# cryobondr-qbit2-pqc-rev2.net
KiCad netlist of a schematic drawn in EAGLE
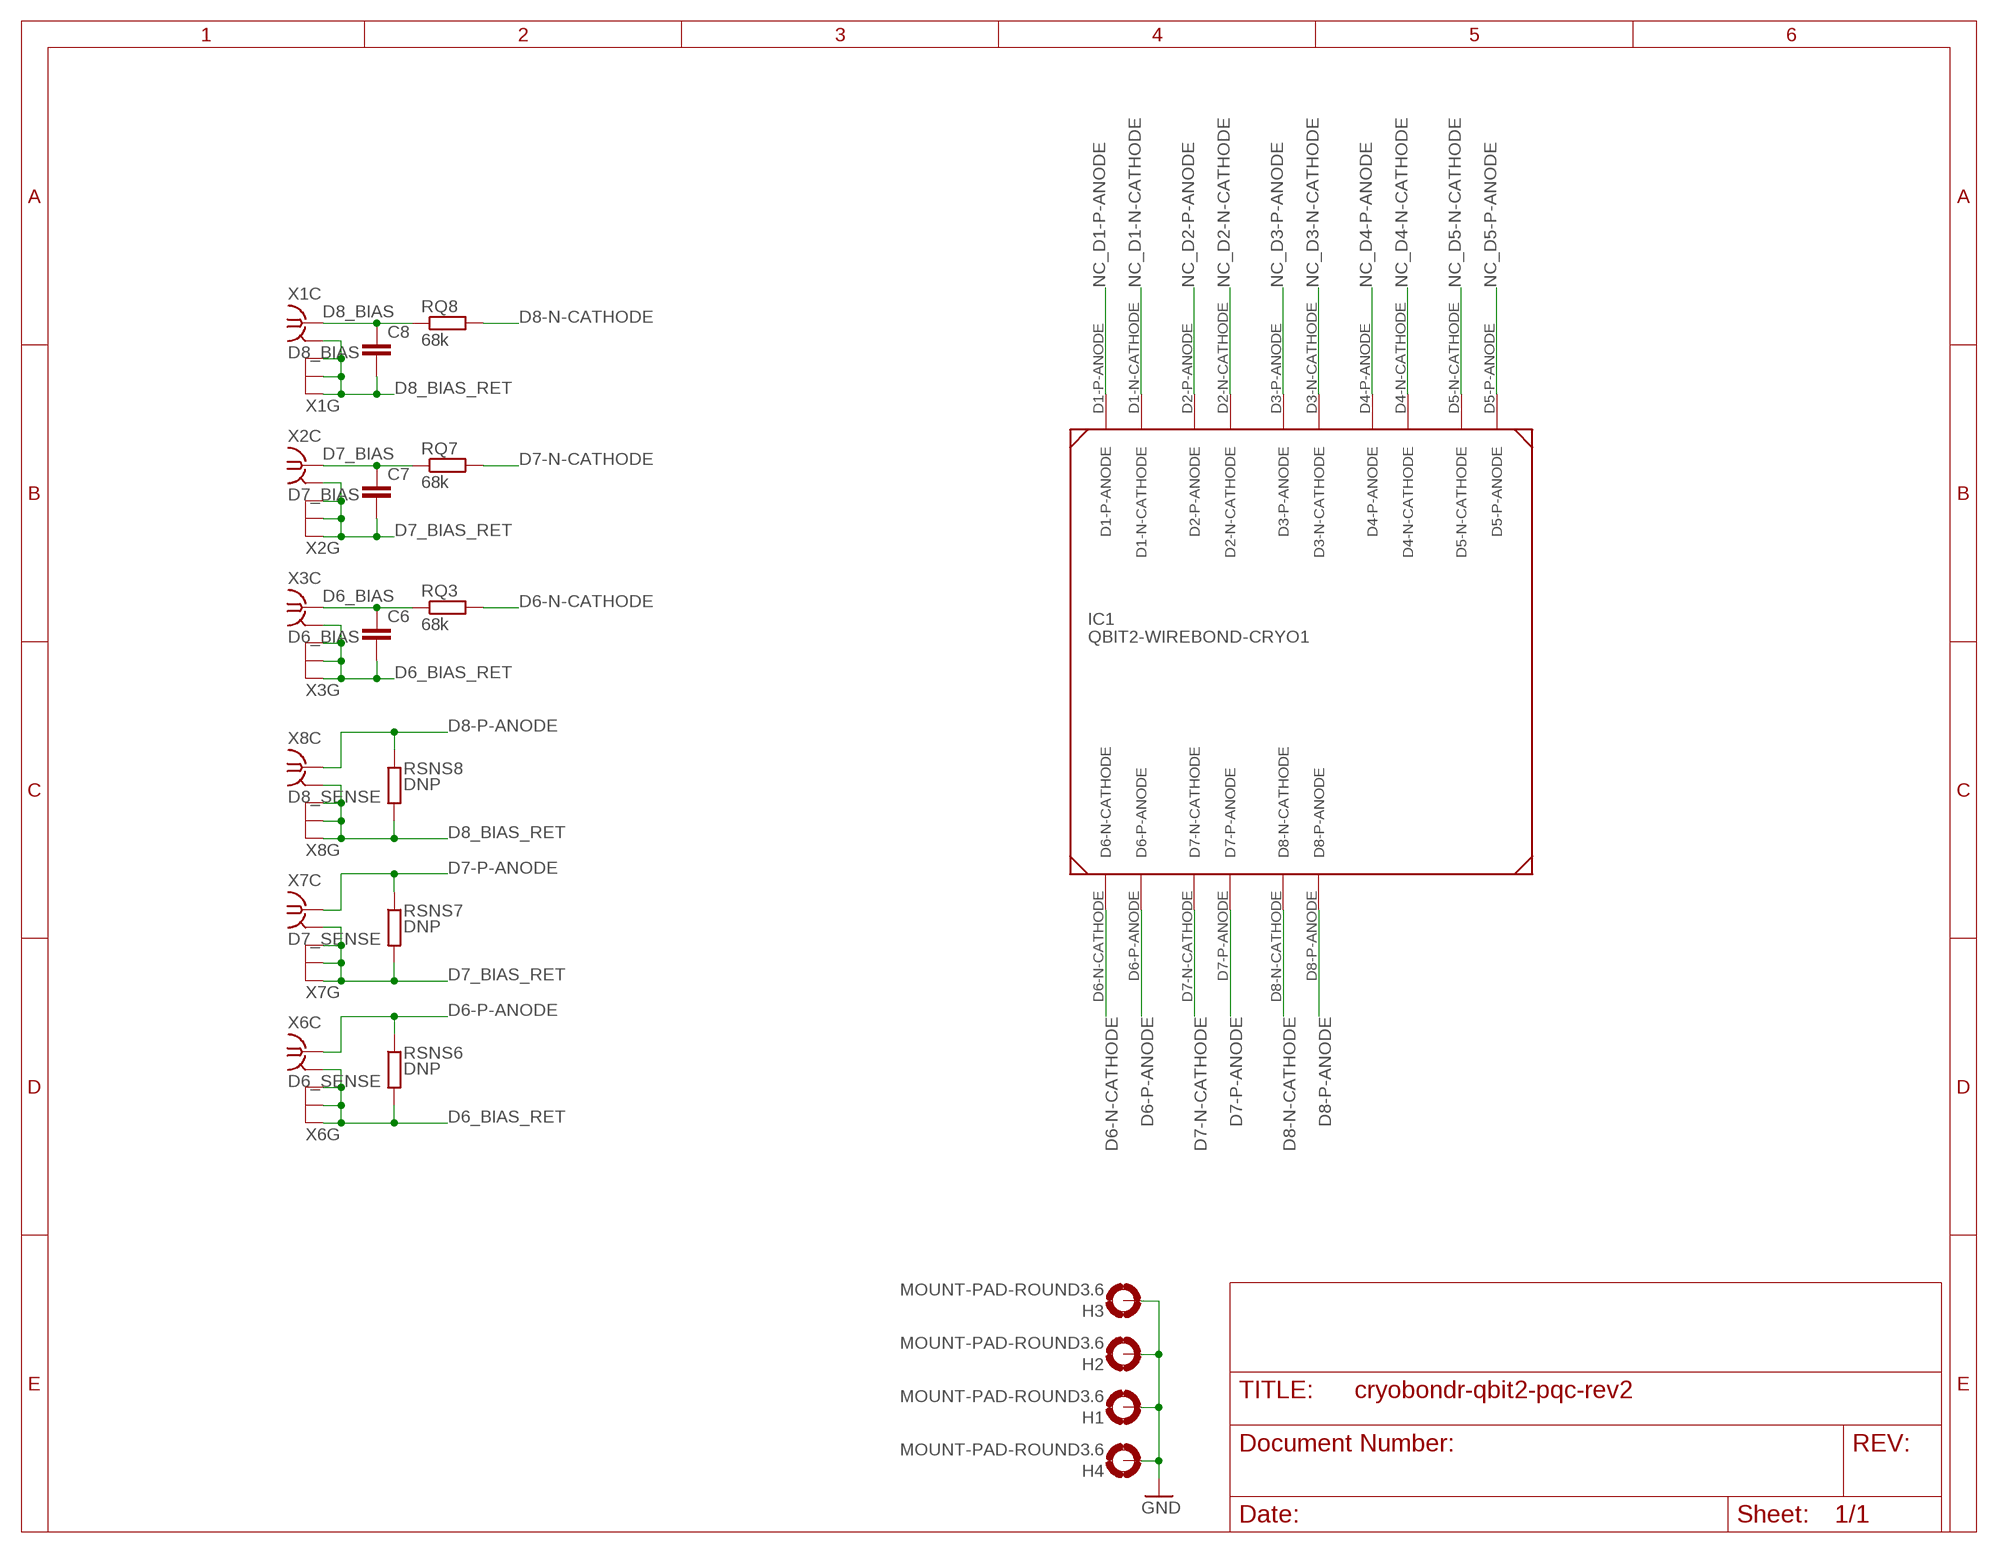
[diagram p0: schematic, sheet 1]

(export (version "E")
  (design (tool "Eeschema 10.0.6"))
  (components
    (comp (ref "C6")
      (value "C-EUC0603")
      (footprint "eagle-import:C0603")
      (libsource (lib "eagle-import") (part "C-EUC0603"))
    )
    (comp (ref "C7")
      (value "C-EUC0603")
      (footprint "eagle-import:C0603")
      (libsource (lib "eagle-import") (part "C-EUC0603"))
    )
    (comp (ref "C8")
      (value "C-EUC0603")
      (footprint "eagle-import:C0603")
      (libsource (lib "eagle-import") (part "C-EUC0603"))
    )
    (comp (ref "H1")
      (value "MOUNT-PAD-ROUND3.6")
      (footprint "eagle-import:3,6-PAD")
      (libsource (lib "eagle-import") (part "MOUNT-PAD-ROUND3.6"))
    )
    (comp (ref "H2")
      (value "MOUNT-PAD-ROUND3.6")
      (footprint "eagle-import:3,6-PAD")
      (libsource (lib "eagle-import") (part "MOUNT-PAD-ROUND3.6"))
    )
    (comp (ref "H3")
      (value "MOUNT-PAD-ROUND3.6")
      (footprint "eagle-import:3,6-PAD")
      (libsource (lib "eagle-import") (part "MOUNT-PAD-ROUND3.6"))
    )
    (comp (ref "H4")
      (value "MOUNT-PAD-ROUND3.6")
      (footprint "eagle-import:3,6-PAD")
      (libsource (lib "eagle-import") (part "MOUNT-PAD-ROUND3.6"))
    )
    (comp (ref "IC1")
      (value "QBIT2-WIREBOND-CRYO1")
      (footprint "eagle-import:QBIT2-WIREBOND-CRYO1")
      (libsource (lib "eagle-import") (part "QBIT2-WIREBOND-CRYO1"))
    )
    (comp (ref "RQ3")
      (value "68k")
      (footprint "eagle-import:R0603")
      (libsource (lib "eagle-import") (part "R-EU_R0603"))
    )
    (comp (ref "RQ7")
      (value "68k")
      (footprint "eagle-import:R0603")
      (libsource (lib "eagle-import") (part "R-EU_R0603"))
    )
    (comp (ref "RQ8")
      (value "68k")
      (footprint "eagle-import:R0603")
      (libsource (lib "eagle-import") (part "R-EU_R0603"))
    )
    (comp (ref "RSNS6")
      (value "DNP")
      (footprint "eagle-import:R0603")
      (libsource (lib "eagle-import") (part "R-EU_R0603"))
    )
    (comp (ref "RSNS7")
      (value "DNP")
      (footprint "eagle-import:R0603")
      (libsource (lib "eagle-import") (part "R-EU_R0603"))
    )
    (comp (ref "RSNS8")
      (value "DNP")
      (footprint "eagle-import:R0603")
      (libsource (lib "eagle-import") (part "R-EU_R0603"))
    )
    (comp (ref "X1")
      (value "D8_BIAS")
      (footprint "eagle-import:MMCX-SMT-BIGPADS")
      (libsource (lib "eagle-import") (part "MMCXBIGPAD"))
    )
    (comp (ref "X2")
      (value "D7_BIAS")
      (footprint "eagle-import:MMCX-SMT-BIGPADS")
      (libsource (lib "eagle-import") (part "MMCXBIGPAD"))
    )
    (comp (ref "X3")
      (value "D6_BIAS")
      (footprint "eagle-import:MMCX-SMT-BIGPADS")
      (libsource (lib "eagle-import") (part "MMCXBIGPAD"))
    )
    (comp (ref "X6")
      (value "D6_SENSE")
      (footprint "eagle-import:MMCX-SMT-BIGPADS")
      (libsource (lib "eagle-import") (part "MMCXBIGPAD"))
    )
    (comp (ref "X7")
      (value "D7_SENSE")
      (footprint "eagle-import:MMCX-SMT-BIGPADS")
      (libsource (lib "eagle-import") (part "MMCXBIGPAD"))
    )
    (comp (ref "X8")
      (value "D8_SENSE")
      (footprint "eagle-import:MMCX-SMT-BIGPADS")
      (libsource (lib "eagle-import") (part "MMCXBIGPAD"))
    )
  )
  (nets
    (net (code "1") (name "/D6-N-CATHODE") (class "Default")
      (node (ref "IC1") (pin "D6-N-CATHODE") (pinfunction "D6-N-CATHODE_D6-N-CATHODE") (pintype "bidirectional"))
      (node (ref "RQ3") (pin "2") (pinfunction "2_2") (pintype "passive"))
    )
    (net (code "2") (name "/D6-P-ANODE") (class "Default")
      (node (ref "IC1") (pin "D6-P-ANODE") (pinfunction "D6-P-ANODE_D6-P-ANODE") (pintype "bidirectional"))
      (node (ref "RSNS6") (pin "1") (pinfunction "1_1") (pintype "passive"))
      (node (ref "X6") (pin "S") (pinfunction "1_S") (pintype "passive"))
    )
    (net (code "3") (name "/D6_BIAS") (class "Default")
      (node (ref "C6") (pin "1") (pinfunction "1_1") (pintype "passive"))
      (node (ref "RQ3") (pin "1") (pinfunction "1_1") (pintype "passive"))
      (node (ref "X3") (pin "S") (pinfunction "1_S") (pintype "passive"))
    )
    (net (code "4") (name "/D6_BIAS_RET") (class "Default")
      (node (ref "C6") (pin "2") (pinfunction "2_2") (pintype "passive"))
      (node (ref "RSNS6") (pin "2") (pinfunction "2_2") (pintype "passive"))
      (node (ref "X3") (pin "G1") (pinfunction "GND_G1") (pintype "power_in"))
      (node (ref "X3") (pin "G2") (pinfunction "GND_G2") (pintype "power_in"))
      (node (ref "X3") (pin "G3") (pinfunction "GND_G3") (pintype "power_in"))
      (node (ref "X3") (pin "G4") (pinfunction "GND_G4") (pintype "power_in"))
      (node (ref "X6") (pin "G1") (pinfunction "GND_G1") (pintype "power_in"))
      (node (ref "X6") (pin "G2") (pinfunction "GND_G2") (pintype "power_in"))
      (node (ref "X6") (pin "G3") (pinfunction "GND_G3") (pintype "power_in"))
      (node (ref "X6") (pin "G4") (pinfunction "GND_G4") (pintype "power_in"))
    )
    (net (code "5") (name "/D7-N-CATHODE") (class "Default")
      (node (ref "IC1") (pin "D7-N-CATHODE") (pinfunction "D7-N-CATHODE_D7-N-CATHODE") (pintype "bidirectional"))
      (node (ref "RQ7") (pin "2") (pinfunction "2_2") (pintype "passive"))
    )
    (net (code "6") (name "/D7-P-ANODE") (class "Default")
      (node (ref "IC1") (pin "D7-P-ANODE") (pinfunction "D7-P-ANODE_D7-P-ANODE") (pintype "bidirectional"))
      (node (ref "RSNS7") (pin "1") (pinfunction "1_1") (pintype "passive"))
      (node (ref "X7") (pin "S") (pinfunction "1_S") (pintype "passive"))
    )
    (net (code "7") (name "/D7_BIAS") (class "Default")
      (node (ref "C7") (pin "1") (pinfunction "1_1") (pintype "passive"))
      (node (ref "RQ7") (pin "1") (pinfunction "1_1") (pintype "passive"))
      (node (ref "X2") (pin "S") (pinfunction "1_S") (pintype "passive"))
    )
    (net (code "8") (name "/D7_BIAS_RET") (class "Default")
      (node (ref "C7") (pin "2") (pinfunction "2_2") (pintype "passive"))
      (node (ref "RSNS7") (pin "2") (pinfunction "2_2") (pintype "passive"))
      (node (ref "X2") (pin "G1") (pinfunction "GND_G1") (pintype "power_in"))
      (node (ref "X2") (pin "G2") (pinfunction "GND_G2") (pintype "power_in"))
      (node (ref "X2") (pin "G3") (pinfunction "GND_G3") (pintype "power_in"))
      (node (ref "X2") (pin "G4") (pinfunction "GND_G4") (pintype "power_in"))
      (node (ref "X7") (pin "G1") (pinfunction "GND_G1") (pintype "power_in"))
      (node (ref "X7") (pin "G2") (pinfunction "GND_G2") (pintype "power_in"))
      (node (ref "X7") (pin "G3") (pinfunction "GND_G3") (pintype "power_in"))
      (node (ref "X7") (pin "G4") (pinfunction "GND_G4") (pintype "power_in"))
    )
    (net (code "9") (name "/D8-N-CATHODE") (class "Default")
      (node (ref "IC1") (pin "D8-N-CATHODE") (pinfunction "D8-N-CATHODE_D8-N-CATHODE") (pintype "bidirectional"))
      (node (ref "RQ8") (pin "2") (pinfunction "2_2") (pintype "passive"))
    )
    (net (code "10") (name "/D8-P-ANODE") (class "Default")
      (node (ref "IC1") (pin "D8-P-ANODE") (pinfunction "D8-P-ANODE_D8-P-ANODE") (pintype "bidirectional"))
      (node (ref "RSNS8") (pin "1") (pinfunction "1_1") (pintype "passive"))
      (node (ref "X8") (pin "S") (pinfunction "1_S") (pintype "passive"))
    )
    (net (code "11") (name "/D8_BIAS") (class "Default")
      (node (ref "C8") (pin "1") (pinfunction "1_1") (pintype "passive"))
      (node (ref "RQ8") (pin "1") (pinfunction "1_1") (pintype "passive"))
      (node (ref "X1") (pin "S") (pinfunction "1_S") (pintype "passive"))
    )
    (net (code "12") (name "/D8_BIAS_RET") (class "Default")
      (node (ref "C8") (pin "2") (pinfunction "2_2") (pintype "passive"))
      (node (ref "RSNS8") (pin "2") (pinfunction "2_2") (pintype "passive"))
      (node (ref "X1") (pin "G1") (pinfunction "GND_G1") (pintype "power_in"))
      (node (ref "X1") (pin "G2") (pinfunction "GND_G2") (pintype "power_in"))
      (node (ref "X1") (pin "G3") (pinfunction "GND_G3") (pintype "power_in"))
      (node (ref "X1") (pin "G4") (pinfunction "GND_G4") (pintype "power_in"))
      (node (ref "X8") (pin "G1") (pinfunction "GND_G1") (pintype "power_in"))
      (node (ref "X8") (pin "G2") (pinfunction "GND_G2") (pintype "power_in"))
      (node (ref "X8") (pin "G3") (pinfunction "GND_G3") (pintype "power_in"))
      (node (ref "X8") (pin "G4") (pinfunction "GND_G4") (pintype "power_in"))
    )
    (net (code "13") (name "/NC_D1-N-CATHODE") (class "Default")
      (node (ref "IC1") (pin "D1-N-CATHODE") (pinfunction "D1-N-CATHODE_D1-N-CATHODE") (pintype "bidirectional"))
    )
    (net (code "14") (name "/NC_D1-P-ANODE") (class "Default")
      (node (ref "IC1") (pin "D1-P-ANODE") (pinfunction "D1-P-ANODE_D1-P-ANODE") (pintype "bidirectional"))
    )
    (net (code "15") (name "/NC_D2-N-CATHODE") (class "Default")
      (node (ref "IC1") (pin "D2-N-CATHODE") (pinfunction "D2-N-CATHODE_D2-N-CATHODE") (pintype "bidirectional"))
    )
    (net (code "16") (name "/NC_D2-P-ANODE") (class "Default")
      (node (ref "IC1") (pin "D2-P-ANODE") (pinfunction "D2-P-ANODE_D2-P-ANODE") (pintype "bidirectional"))
    )
    (net (code "17") (name "/NC_D3-N-CATHODE") (class "Default")
      (node (ref "IC1") (pin "D3-N-CATHODE") (pinfunction "D3-N-CATHODE_D3-N-CATHODE") (pintype "bidirectional"))
    )
    (net (code "18") (name "/NC_D3-P-ANODE") (class "Default")
      (node (ref "IC1") (pin "D3-P-ANODE") (pinfunction "D3-P-ANODE_D3-P-ANODE") (pintype "bidirectional"))
    )
    (net (code "19") (name "/NC_D4-N-CATHODE") (class "Default")
      (node (ref "IC1") (pin "D4-N-CATHODE") (pinfunction "D4-N-CATHODE_D4-N-CATHODE") (pintype "bidirectional"))
    )
    (net (code "20") (name "/NC_D4-P-ANODE") (class "Default")
      (node (ref "IC1") (pin "D4-P-ANODE") (pinfunction "D4-P-ANODE_D4-P-ANODE") (pintype "bidirectional"))
    )
    (net (code "21") (name "/NC_D5-N-CATHODE") (class "Default")
      (node (ref "IC1") (pin "D5-N-CATHODE") (pinfunction "D5-N-CATHODE_D5-N-CATHODE") (pintype "bidirectional"))
    )
    (net (code "22") (name "/NC_D5-P-ANODE") (class "Default")
      (node (ref "IC1") (pin "D5-P-ANODE") (pinfunction "D5-P-ANODE_D5-P-ANODE") (pintype "bidirectional"))
    )
    (net (code "23") (name "GND") (class "Default")
      (node (ref "H1") (pin "B3,6") (pinfunction "MOUNT_B3,6") (pintype "passive"))
      (node (ref "H2") (pin "B3,6") (pinfunction "MOUNT_B3,6") (pintype "passive"))
      (node (ref "H3") (pin "B3,6") (pinfunction "MOUNT_B3,6") (pintype "passive"))
      (node (ref "H4") (pin "B3,6") (pinfunction "MOUNT_B3,6") (pintype "passive"))
    )
  )
)
